# 04_Inputs_19-27.net
KiCad netlist of a schematic drawn in Altium Designer
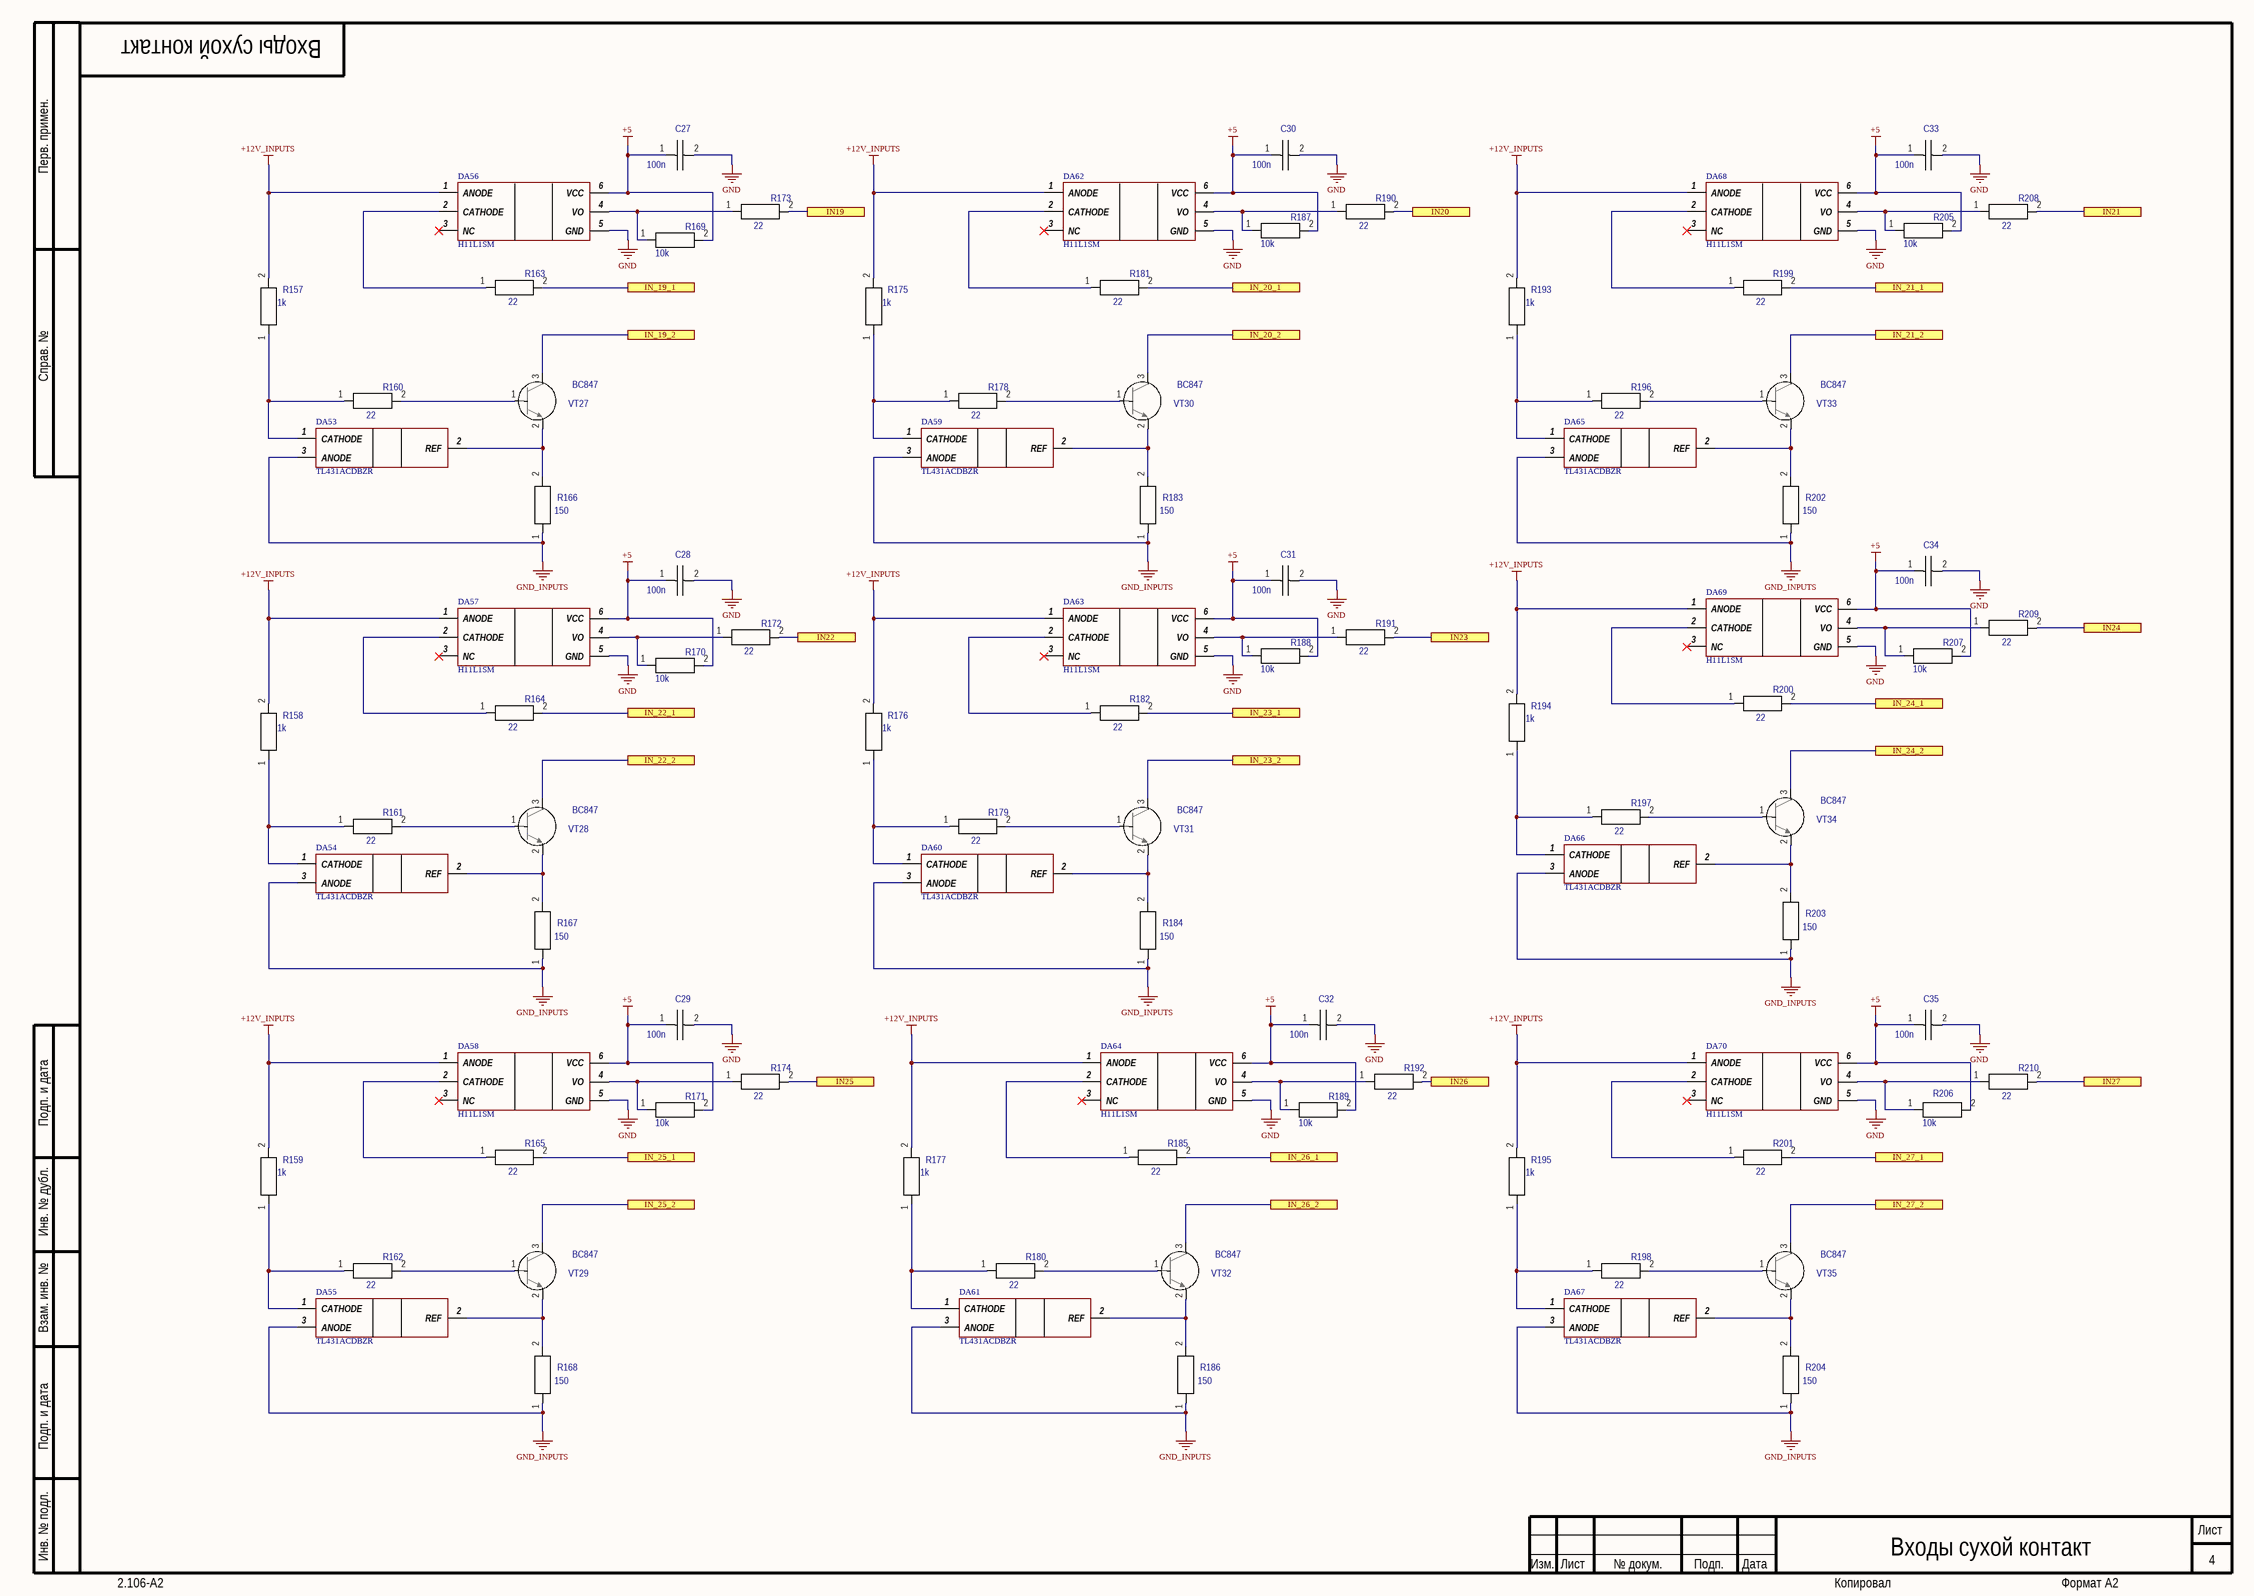
[diagram p0: 04_Inputs_19-27.SchDoc]

(export (version "E")
  (design (tool "Eeschema 10.0.6"))
  (components
    (comp (ref "C27")
      (value "100n")
      (footprint "C0603")
      (fields
        (field (name "PART NUMBER") "GRM188R71C104KA01D")
        (field (name "TOLERANCE") "±10%")
        (field (name "MANUFACTURER") "Murata Manufacturing")
      )
      (libsource (lib "AccessLibrary") (part "Capacitor"))
    )
    (comp (ref "C28")
      (value "100n")
      (footprint "C0603")
      (fields
        (field (name "PART NUMBER") "GRM188R71C104KA01D")
        (field (name "TOLERANCE") "±10%")
        (field (name "MANUFACTURER") "Murata Manufacturing")
      )
      (libsource (lib "AccessLibrary") (part "Capacitor"))
    )
    (comp (ref "C29")
      (value "100n")
      (footprint "C0603")
      (fields
        (field (name "PART NUMBER") "GRM188R71C104KA01D")
        (field (name "TOLERANCE") "±10%")
        (field (name "MANUFACTURER") "Murata Manufacturing")
      )
      (libsource (lib "AccessLibrary") (part "Capacitor"))
    )
    (comp (ref "C30")
      (value "100n")
      (footprint "C0603")
      (fields
        (field (name "PART NUMBER") "GRM188R71C104KA01D")
        (field (name "TOLERANCE") "±10%")
        (field (name "MANUFACTURER") "Murata Manufacturing")
      )
      (libsource (lib "AccessLibrary") (part "Capacitor"))
    )
    (comp (ref "C31")
      (value "100n")
      (footprint "C0603")
      (fields
        (field (name "PART NUMBER") "GRM188R71C104KA01D")
        (field (name "TOLERANCE") "±10%")
        (field (name "MANUFACTURER") "Murata Manufacturing")
      )
      (libsource (lib "AccessLibrary") (part "Capacitor"))
    )
    (comp (ref "C32")
      (value "100n")
      (footprint "C0603")
      (fields
        (field (name "PART NUMBER") "GRM188R71C104KA01D")
        (field (name "TOLERANCE") "±10%")
        (field (name "MANUFACTURER") "Murata Manufacturing")
      )
      (libsource (lib "AccessLibrary") (part "Capacitor"))
    )
    (comp (ref "C33")
      (value "100n")
      (footprint "C0603")
      (fields
        (field (name "PART NUMBER") "GRM188R71C104KA01D")
        (field (name "TOLERANCE") "±10%")
        (field (name "MANUFACTURER") "Murata Manufacturing")
      )
      (libsource (lib "AccessLibrary") (part "Capacitor"))
    )
    (comp (ref "C34")
      (value "100n")
      (footprint "C0603")
      (fields
        (field (name "PART NUMBER") "GRM188R71C104KA01D")
        (field (name "TOLERANCE") "±10%")
        (field (name "MANUFACTURER") "Murata Manufacturing")
      )
      (libsource (lib "AccessLibrary") (part "Capacitor"))
    )
    (comp (ref "C35")
      (value "100n")
      (footprint "C0603")
      (fields
        (field (name "PART NUMBER") "GRM188R71C104KA01D")
        (field (name "TOLERANCE") "±10%")
        (field (name "MANUFACTURER") "Murata Manufacturing")
      )
      (libsource (lib "AccessLibrary") (part "Capacitor"))
    )
    (comp (ref "DA53")
      (value "TL431ACDBZR")
      (footprint "board:SOT95P237X112-3N")
      (description "Integrated Circuit")
      (fields (field (name "MOUSER PART NUMBER") "595-TL431ACDBZR"))
      (libsource (lib "board") (part "TL431ACDBZR"))
    )
    (comp (ref "DA54")
      (value "TL431ACDBZR")
      (footprint "board:SOT95P237X112-3N")
      (description "Integrated Circuit")
      (fields (field (name "MOUSER PART NUMBER") "595-TL431ACDBZR"))
      (libsource (lib "board") (part "TL431ACDBZR"))
    )
    (comp (ref "DA55")
      (value "TL431ACDBZR")
      (footprint "board:SOT95P237X112-3N")
      (description "Integrated Circuit")
      (fields (field (name "MOUSER PART NUMBER") "595-TL431ACDBZR"))
      (libsource (lib "board") (part "TL431ACDBZR"))
    )
    (comp (ref "DA56")
      (value "H11L1SM")
      (footprint "board:SOP254P1030X460-6N")
      (description "Integrated Circuit")
      (libsource (lib "board") (part "H11L1SM"))
    )
    (comp (ref "DA57")
      (value "H11L1SM")
      (footprint "board:SOP254P1030X460-6N")
      (description "Integrated Circuit")
      (libsource (lib "board") (part "H11L1SM"))
    )
    (comp (ref "DA58")
      (value "H11L1SM")
      (footprint "board:SOP254P1030X460-6N")
      (description "Integrated Circuit")
      (libsource (lib "board") (part "H11L1SM"))
    )
    (comp (ref "DA59")
      (value "TL431ACDBZR")
      (footprint "board:SOT95P237X112-3N")
      (description "Integrated Circuit")
      (fields (field (name "MOUSER PART NUMBER") "595-TL431ACDBZR"))
      (libsource (lib "board") (part "TL431ACDBZR"))
    )
    (comp (ref "DA60")
      (value "TL431ACDBZR")
      (footprint "board:SOT95P237X112-3N")
      (description "Integrated Circuit")
      (fields (field (name "MOUSER PART NUMBER") "595-TL431ACDBZR"))
      (libsource (lib "board") (part "TL431ACDBZR"))
    )
    (comp (ref "DA61")
      (value "TL431ACDBZR")
      (footprint "board:SOT95P237X112-3N")
      (description "Integrated Circuit")
      (fields (field (name "MOUSER PART NUMBER") "595-TL431ACDBZR"))
      (libsource (lib "board") (part "TL431ACDBZR"))
    )
    (comp (ref "DA62")
      (value "H11L1SM")
      (footprint "board:SOP254P1030X460-6N")
      (description "Integrated Circuit")
      (libsource (lib "board") (part "H11L1SM"))
    )
    (comp (ref "DA63")
      (value "H11L1SM")
      (footprint "board:SOP254P1030X460-6N")
      (description "Integrated Circuit")
      (libsource (lib "board") (part "H11L1SM"))
    )
    (comp (ref "DA64")
      (value "H11L1SM")
      (footprint "board:SOP254P1030X460-6N")
      (description "Integrated Circuit")
      (libsource (lib "board") (part "H11L1SM"))
    )
    (comp (ref "DA65")
      (value "TL431ACDBZR")
      (footprint "board:SOT95P237X112-3N")
      (description "Integrated Circuit")
      (fields (field (name "MOUSER PART NUMBER") "595-TL431ACDBZR"))
      (libsource (lib "board") (part "TL431ACDBZR"))
    )
    (comp (ref "DA66")
      (value "TL431ACDBZR")
      (footprint "board:SOT95P237X112-3N")
      (description "Integrated Circuit")
      (fields (field (name "MOUSER PART NUMBER") "595-TL431ACDBZR"))
      (libsource (lib "board") (part "TL431ACDBZR"))
    )
    (comp (ref "DA67")
      (value "TL431ACDBZR")
      (footprint "board:SOT95P237X112-3N")
      (description "Integrated Circuit")
      (fields (field (name "MOUSER PART NUMBER") "595-TL431ACDBZR"))
      (libsource (lib "board") (part "TL431ACDBZR"))
    )
    (comp (ref "DA68")
      (value "H11L1SM")
      (footprint "board:SOP254P1030X460-6N")
      (description "Integrated Circuit")
      (libsource (lib "board") (part "H11L1SM"))
    )
    (comp (ref "DA69")
      (value "H11L1SM")
      (footprint "board:SOP254P1030X460-6N")
      (description "Integrated Circuit")
      (libsource (lib "board") (part "H11L1SM"))
    )
    (comp (ref "DA70")
      (value "H11L1SM")
      (footprint "board:SOP254P1030X460-6N")
      (description "Integrated Circuit")
      (libsource (lib "board") (part "H11L1SM"))
    )
    (comp (ref "R157")
      (value "1k")
      (footprint "RESC1608N")
      (fields
        (field (name "PART NUMBER") "RC0603FK-071KL")
        (field (name "TOLERANCE") "±1%")
        (field (name "MANUFACTURER") "Тайвань")
      )
      (libsource (lib "AccessLibrary") (part "Resistor"))
    )
    (comp (ref "R158")
      (value "1k")
      (footprint "RESC1608N")
      (fields
        (field (name "PART NUMBER") "RC0603FK-071KL")
        (field (name "TOLERANCE") "±1%")
        (field (name "MANUFACTURER") "Тайвань")
      )
      (libsource (lib "AccessLibrary") (part "Resistor"))
    )
    (comp (ref "R159")
      (value "1k")
      (footprint "RESC1608N")
      (fields
        (field (name "PART NUMBER") "RC0603FK-071KL")
        (field (name "TOLERANCE") "±1%")
        (field (name "MANUFACTURER") "Тайвань")
      )
      (libsource (lib "AccessLibrary") (part "Resistor"))
    )
    (comp (ref "R160")
      (value "22")
      (footprint "RESC1608N")
      (fields
        (field (name "PART NUMBER") "RC0603FK-0722RL")
        (field (name "TOLERANCE") "±1%")
        (field (name "MANUFACTURER") "Тайвань")
      )
      (libsource (lib "AccessLibrary") (part "Resistor"))
    )
    (comp (ref "R161")
      (value "22")
      (footprint "RESC1608N")
      (fields
        (field (name "PART NUMBER") "RC0603FK-0722RL")
        (field (name "TOLERANCE") "±1%")
        (field (name "MANUFACTURER") "Тайвань")
      )
      (libsource (lib "AccessLibrary") (part "Resistor"))
    )
    (comp (ref "R162")
      (value "22")
      (footprint "RESC1608N")
      (fields
        (field (name "PART NUMBER") "RC0603FK-0722RL")
        (field (name "TOLERANCE") "±1%")
        (field (name "MANUFACTURER") "Тайвань")
      )
      (libsource (lib "AccessLibrary") (part "Resistor"))
    )
    (comp (ref "R163")
      (value "22")
      (footprint "RESC1608N")
      (fields
        (field (name "PART NUMBER") "RC0603FK-0722RL")
        (field (name "TOLERANCE") "±1%")
        (field (name "MANUFACTURER") "Тайвань")
      )
      (libsource (lib "AccessLibrary") (part "Resistor"))
    )
    (comp (ref "R164")
      (value "22")
      (footprint "RESC1608N")
      (fields
        (field (name "PART NUMBER") "RC0603FK-0722RL")
        (field (name "TOLERANCE") "±1%")
        (field (name "MANUFACTURER") "Тайвань")
      )
      (libsource (lib "AccessLibrary") (part "Resistor"))
    )
    (comp (ref "R165")
      (value "22")
      (footprint "RESC1608N")
      (fields
        (field (name "PART NUMBER") "RC0603FK-0722RL")
        (field (name "TOLERANCE") "±1%")
        (field (name "MANUFACTURER") "Тайвань")
      )
      (libsource (lib "AccessLibrary") (part "Resistor"))
    )
    (comp (ref "R166")
      (value "150")
      (footprint "RESC1608N")
      (fields
        (field (name "PART NUMBER") "RC0603FK-07150RL")
        (field (name "TOLERANCE") "±1%")
        (field (name "MANUFACTURER") "Тайвань")
      )
      (libsource (lib "AccessLibrary") (part "Resistor"))
    )
    (comp (ref "R167")
      (value "150")
      (footprint "RESC1608N")
      (fields
        (field (name "PART NUMBER") "RC0603FK-07150RL")
        (field (name "TOLERANCE") "±1%")
        (field (name "MANUFACTURER") "Тайвань")
      )
      (libsource (lib "AccessLibrary") (part "Resistor"))
    )
    (comp (ref "R168")
      (value "150")
      (footprint "RESC1608N")
      (fields
        (field (name "PART NUMBER") "RC0603FK-07150RL")
        (field (name "TOLERANCE") "±1%")
        (field (name "MANUFACTURER") "Тайвань")
      )
      (libsource (lib "AccessLibrary") (part "Resistor"))
    )
    (comp (ref "R169")
      (value "10k")
      (footprint "RESC1608N")
      (fields
        (field (name "PART NUMBER") "RC0603FR-0710KL")
        (field (name "TOLERANCE") "±1%")
        (field (name "MANUFACTURER") "Тайвань")
      )
      (libsource (lib "AccessLibrary") (part "Resistor"))
    )
    (comp (ref "R170")
      (value "10k")
      (footprint "RESC1608N")
      (fields
        (field (name "PART NUMBER") "RC0603FR-0710KL")
        (field (name "TOLERANCE") "±1%")
        (field (name "MANUFACTURER") "Тайвань")
      )
      (libsource (lib "AccessLibrary") (part "Resistor"))
    )
    (comp (ref "R171")
      (value "10k")
      (footprint "RESC1608N")
      (fields
        (field (name "PART NUMBER") "RC0603FR-0710KL")
        (field (name "TOLERANCE") "±1%")
        (field (name "MANUFACTURER") "Тайвань")
      )
      (libsource (lib "AccessLibrary") (part "Resistor"))
    )
    (comp (ref "R172")
      (value "22")
      (footprint "RESC1608N")
      (fields
        (field (name "PART NUMBER") "RC0603FK-0722RL")
        (field (name "TOLERANCE") "±1%")
        (field (name "MANUFACTURER") "Тайвань")
      )
      (libsource (lib "AccessLibrary") (part "Resistor"))
    )
    (comp (ref "R173")
      (value "22")
      (footprint "RESC1608N")
      (fields
        (field (name "PART NUMBER") "RC0603FK-0722RL")
        (field (name "TOLERANCE") "±1%")
        (field (name "MANUFACTURER") "Тайвань")
      )
      (libsource (lib "AccessLibrary") (part "Resistor"))
    )
    (comp (ref "R174")
      (value "22")
      (footprint "RESC1608N")
      (fields
        (field (name "PART NUMBER") "RC0603FK-0722RL")
        (field (name "TOLERANCE") "±1%")
        (field (name "MANUFACTURER") "Тайвань")
      )
      (libsource (lib "AccessLibrary") (part "Resistor"))
    )
    (comp (ref "R175")
      (value "1k")
      (footprint "RESC1608N")
      (fields
        (field (name "PART NUMBER") "RC0603FK-071KL")
        (field (name "TOLERANCE") "±1%")
        (field (name "MANUFACTURER") "Тайвань")
      )
      (libsource (lib "AccessLibrary") (part "Resistor"))
    )
    (comp (ref "R176")
      (value "1k")
      (footprint "RESC1608N")
      (fields
        (field (name "PART NUMBER") "RC0603FK-071KL")
        (field (name "TOLERANCE") "±1%")
        (field (name "MANUFACTURER") "Тайвань")
      )
      (libsource (lib "AccessLibrary") (part "Resistor"))
    )
    (comp (ref "R177")
      (value "1k")
      (footprint "RESC1608N")
      (fields
        (field (name "PART NUMBER") "RC0603FK-071KL")
        (field (name "TOLERANCE") "±1%")
        (field (name "MANUFACTURER") "Тайвань")
      )
      (libsource (lib "AccessLibrary") (part "Resistor"))
    )
    (comp (ref "R178")
      (value "22")
      (footprint "RESC1608N")
      (fields
        (field (name "PART NUMBER") "RC0603FK-0722RL")
        (field (name "TOLERANCE") "±1%")
        (field (name "MANUFACTURER") "Тайвань")
      )
      (libsource (lib "AccessLibrary") (part "Resistor"))
    )
    (comp (ref "R179")
      (value "22")
      (footprint "RESC1608N")
      (fields
        (field (name "PART NUMBER") "RC0603FK-0722RL")
        (field (name "TOLERANCE") "±1%")
        (field (name "MANUFACTURER") "Тайвань")
      )
      (libsource (lib "AccessLibrary") (part "Resistor"))
    )
    (comp (ref "R180")
      (value "22")
      (footprint "RESC1608N")
      (fields
        (field (name "PART NUMBER") "RC0603FK-0722RL")
        (field (name "TOLERANCE") "±1%")
        (field (name "MANUFACTURER") "Тайвань")
      )
      (libsource (lib "AccessLibrary") (part "Resistor"))
    )
    (comp (ref "R181")
      (value "22")
      (footprint "RESC1608N")
      (fields
        (field (name "PART NUMBER") "RC0603FK-0722RL")
        (field (name "TOLERANCE") "±1%")
        (field (name "MANUFACTURER") "Тайвань")
      )
      (libsource (lib "AccessLibrary") (part "Resistor"))
    )
    (comp (ref "R182")
      (value "22")
      (footprint "RESC1608N")
      (fields
        (field (name "PART NUMBER") "RC0603FK-0722RL")
        (field (name "TOLERANCE") "±1%")
        (field (name "MANUFACTURER") "Тайвань")
      )
      (libsource (lib "AccessLibrary") (part "Resistor"))
    )
    (comp (ref "R183")
      (value "150")
      (footprint "RESC1608N")
      (fields
        (field (name "PART NUMBER") "RC0603FK-07150RL")
        (field (name "TOLERANCE") "±1%")
        (field (name "MANUFACTURER") "Тайвань")
      )
      (libsource (lib "AccessLibrary") (part "Resistor"))
    )
    (comp (ref "R184")
      (value "150")
      (footprint "RESC1608N")
      (fields
        (field (name "PART NUMBER") "RC0603FK-07150RL")
        (field (name "TOLERANCE") "±1%")
        (field (name "MANUFACTURER") "Тайвань")
      )
      (libsource (lib "AccessLibrary") (part "Resistor"))
    )
    (comp (ref "R185")
      (value "22")
      (footprint "RESC1608N")
      (fields
        (field (name "PART NUMBER") "RC0603FK-0722RL")
        (field (name "TOLERANCE") "±1%")
        (field (name "MANUFACTURER") "Тайвань")
      )
      (libsource (lib "AccessLibrary") (part "Resistor"))
    )
    (comp (ref "R186")
      (value "150")
      (footprint "RESC1608N")
      (fields
        (field (name "PART NUMBER") "RC0603FK-07150RL")
        (field (name "TOLERANCE") "±1%")
        (field (name "MANUFACTURER") "Тайвань")
      )
      (libsource (lib "AccessLibrary") (part "Resistor"))
    )
    (comp (ref "R187")
      (value "10k")
      (footprint "RESC1608N")
      (fields
        (field (name "PART NUMBER") "RC0603FR-0710KL")
        (field (name "TOLERANCE") "±1%")
        (field (name "MANUFACTURER") "Тайвань")
      )
      (libsource (lib "AccessLibrary") (part "Resistor"))
    )
    (comp (ref "R188")
      (value "10k")
      (footprint "RESC1608N")
      (fields
        (field (name "PART NUMBER") "RC0603FR-0710KL")
        (field (name "TOLERANCE") "±1%")
        (field (name "MANUFACTURER") "Тайвань")
      )
      (libsource (lib "AccessLibrary") (part "Resistor"))
    )
    (comp (ref "R189")
      (value "10k")
      (footprint "RESC1608N")
      (fields
        (field (name "PART NUMBER") "RC0603FR-0710KL")
        (field (name "TOLERANCE") "±1%")
        (field (name "MANUFACTURER") "Тайвань")
      )
      (libsource (lib "AccessLibrary") (part "Resistor"))
    )
    (comp (ref "R190")
      (value "22")
      (footprint "RESC1608N")
      (fields
        (field (name "PART NUMBER") "RC0603FK-0722RL")
        (field (name "TOLERANCE") "±1%")
        (field (name "MANUFACTURER") "Тайвань")
      )
      (libsource (lib "AccessLibrary") (part "Resistor"))
    )
    (comp (ref "R191")
      (value "22")
      (footprint "RESC1608N")
      (fields
        (field (name "PART NUMBER") "RC0603FK-0722RL")
        (field (name "TOLERANCE") "±1%")
        (field (name "MANUFACTURER") "Тайвань")
      )
      (libsource (lib "AccessLibrary") (part "Resistor"))
    )
    (comp (ref "R192")
      (value "22")
      (footprint "RESC1608N")
      (fields
        (field (name "PART NUMBER") "RC0603FK-0722RL")
        (field (name "TOLERANCE") "±1%")
        (field (name "MANUFACTURER") "Тайвань")
      )
      (libsource (lib "AccessLibrary") (part "Resistor"))
    )
    (comp (ref "R193")
      (value "1k")
      (footprint "RESC1608N")
      (fields
        (field (name "PART NUMBER") "RC0603FK-071KL")
        (field (name "TOLERANCE") "±1%")
        (field (name "MANUFACTURER") "Тайвань")
      )
      (libsource (lib "AccessLibrary") (part "Resistor"))
    )
    (comp (ref "R194")
      (value "1k")
      (footprint "RESC1608N")
      (fields
        (field (name "PART NUMBER") "RC0603FK-071KL")
        (field (name "TOLERANCE") "±1%")
        (field (name "MANUFACTURER") "Тайвань")
      )
      (libsource (lib "AccessLibrary") (part "Resistor"))
    )
    (comp (ref "R195")
      (value "1k")
      (footprint "RESC1608N")
      (fields
        (field (name "PART NUMBER") "RC0603FK-071KL")
        (field (name "TOLERANCE") "±1%")
        (field (name "MANUFACTURER") "Тайвань")
      )
      (libsource (lib "AccessLibrary") (part "Resistor"))
    )
    (comp (ref "R196")
      (value "22")
      (footprint "RESC1608N")
      (fields
        (field (name "PART NUMBER") "RC0603FK-0722RL")
        (field (name "TOLERANCE") "±1%")
        (field (name "MANUFACTURER") "Тайвань")
      )
      (libsource (lib "AccessLibrary") (part "Resistor"))
    )
    (comp (ref "R197")
      (value "22")
      (footprint "RESC1608N")
      (fields
        (field (name "PART NUMBER") "RC0603FK-0722RL")
        (field (name "TOLERANCE") "±1%")
        (field (name "MANUFACTURER") "Тайвань")
      )
      (libsource (lib "AccessLibrary") (part "Resistor"))
    )
    (comp (ref "R198")
      (value "22")
      (footprint "RESC1608N")
      (fields
        (field (name "PART NUMBER") "RC0603FK-0722RL")
        (field (name "TOLERANCE") "±1%")
        (field (name "MANUFACTURER") "Тайвань")
      )
      (libsource (lib "AccessLibrary") (part "Resistor"))
    )
    (comp (ref "R199")
      (value "22")
      (footprint "RESC1608N")
      (fields
        (field (name "PART NUMBER") "RC0603FK-0722RL")
        (field (name "TOLERANCE") "±1%")
        (field (name "MANUFACTURER") "Тайвань")
      )
      (libsource (lib "AccessLibrary") (part "Resistor"))
    )
    (comp (ref "R200")
      (value "22")
      (footprint "RESC1608N")
      (fields
        (field (name "PART NUMBER") "RC0603FK-0722RL")
        (field (name "TOLERANCE") "±1%")
        (field (name "MANUFACTURER") "Тайвань")
      )
      (libsource (lib "AccessLibrary") (part "Resistor"))
    )
    (comp (ref "R201")
      (value "22")
      (footprint "RESC1608N")
      (fields
        (field (name "PART NUMBER") "RC0603FK-0722RL")
        (field (name "TOLERANCE") "±1%")
        (field (name "MANUFACTURER") "Тайвань")
      )
      (libsource (lib "AccessLibrary") (part "Resistor"))
    )
    (comp (ref "R202")
      (value "150")
      (footprint "RESC1608N")
      (fields
        (field (name "PART NUMBER") "RC0603FK-07150RL")
        (field (name "TOLERANCE") "±1%")
        (field (name "MANUFACTURER") "Тайвань")
      )
      (libsource (lib "AccessLibrary") (part "Resistor"))
    )
    (comp (ref "R203")
      (value "150")
      (footprint "RESC1608N")
      (fields
        (field (name "PART NUMBER") "RC0603FK-07150RL")
        (field (name "TOLERANCE") "±1%")
        (field (name "MANUFACTURER") "Тайвань")
      )
      (libsource (lib "AccessLibrary") (part "Resistor"))
    )
    (comp (ref "R204")
      (value "150")
      (footprint "RESC1608N")
      (fields
        (field (name "PART NUMBER") "RC0603FK-07150RL")
        (field (name "TOLERANCE") "±1%")
        (field (name "MANUFACTURER") "Тайвань")
      )
      (libsource (lib "AccessLibrary") (part "Resistor"))
    )
    (comp (ref "R205")
      (value "10k")
      (footprint "RESC1608N")
      (fields
        (field (name "PART NUMBER") "RC0603FR-0710KL")
        (field (name "TOLERANCE") "±1%")
        (field (name "MANUFACTURER") "Тайвань")
      )
      (libsource (lib "AccessLibrary") (part "Resistor"))
    )
    (comp (ref "R206")
      (value "10k")
      (footprint "RESC1608N")
      (fields
        (field (name "PART NUMBER") "RC0603FR-0710KL")
        (field (name "TOLERANCE") "±1%")
        (field (name "MANUFACTURER") "Тайвань")
      )
      (libsource (lib "AccessLibrary") (part "Resistor"))
    )
    (comp (ref "R207")
      (value "10k")
      (footprint "RESC1608N")
      (fields
        (field (name "PART NUMBER") "RC0603FR-0710KL")
        (field (name "TOLERANCE") "±1%")
        (field (name "MANUFACTURER") "Тайвань")
      )
      (libsource (lib "AccessLibrary") (part "Resistor"))
    )
    (comp (ref "R208")
      (value "22")
      (footprint "RESC1608N")
      (fields
        (field (name "PART NUMBER") "RC0603FK-0722RL")
        (field (name "TOLERANCE") "±1%")
        (field (name "MANUFACTURER") "Тайвань")
      )
      (libsource (lib "AccessLibrary") (part "Resistor"))
    )
    (comp (ref "R209")
      (value "22")
      (footprint "RESC1608N")
      (fields
        (field (name "PART NUMBER") "RC0603FK-0722RL")
        (field (name "TOLERANCE") "±1%")
        (field (name "MANUFACTURER") "Тайвань")
      )
      (libsource (lib "AccessLibrary") (part "Resistor"))
    )
    (comp (ref "R210")
      (value "22")
      (footprint "RESC1608N")
      (fields
        (field (name "PART NUMBER") "RC0603FK-0722RL")
        (field (name "TOLERANCE") "±1%")
        (field (name "MANUFACTURER") "Тайвань")
      )
      (libsource (lib "AccessLibrary") (part "Resistor"))
    )
    (comp (ref "VT27")
      (value "BC847")
      (footprint "SOT23-3N")
      (fields (field (name "COM") "BC847") (field (name "MANUFACTURER") "NXP Semiconductor"))
      (libsource (lib "AccessLibrary") (part "Transistor_npn_1b-2e-3c"))
    )
    (comp (ref "VT28")
      (value "BC847")
      (footprint "SOT23-3N")
      (fields (field (name "COM") "BC847") (field (name "MANUFACTURER") "NXP Semiconductor"))
      (libsource (lib "AccessLibrary") (part "Transistor_npn_1b-2e-3c"))
    )
    (comp (ref "VT29")
      (value "BC847")
      (footprint "SOT23-3N")
      (fields (field (name "COM") "BC847") (field (name "MANUFACTURER") "NXP Semiconductor"))
      (libsource (lib "AccessLibrary") (part "Transistor_npn_1b-2e-3c"))
    )
    (comp (ref "VT30")
      (value "BC847")
      (footprint "SOT23-3N")
      (fields (field (name "COM") "BC847") (field (name "MANUFACTURER") "NXP Semiconductor"))
      (libsource (lib "AccessLibrary") (part "Transistor_npn_1b-2e-3c"))
    )
    (comp (ref "VT31")
      (value "BC847")
      (footprint "SOT23-3N")
      (fields (field (name "COM") "BC847") (field (name "MANUFACTURER") "NXP Semiconductor"))
      (libsource (lib "AccessLibrary") (part "Transistor_npn_1b-2e-3c"))
    )
    (comp (ref "VT32")
      (value "BC847")
      (footprint "SOT23-3N")
      (fields (field (name "COM") "BC847") (field (name "MANUFACTURER") "NXP Semiconductor"))
      (libsource (lib "AccessLibrary") (part "Transistor_npn_1b-2e-3c"))
    )
    (comp (ref "VT33")
      (value "BC847")
      (footprint "SOT23-3N")
      (fields (field (name "COM") "BC847") (field (name "MANUFACTURER") "NXP Semiconductor"))
      (libsource (lib "AccessLibrary") (part "Transistor_npn_1b-2e-3c"))
    )
    (comp (ref "VT34")
      (value "BC847")
      (footprint "SOT23-3N")
      (fields (field (name "COM") "BC847") (field (name "MANUFACTURER") "NXP Semiconductor"))
      (libsource (lib "AccessLibrary") (part "Transistor_npn_1b-2e-3c"))
    )
    (comp (ref "VT35")
      (value "BC847")
      (footprint "SOT23-3N")
      (fields (field (name "COM") "BC847") (field (name "MANUFACTURER") "NXP Semiconductor"))
      (libsource (lib "AccessLibrary") (part "Transistor_npn_1b-2e-3c"))
    )
  )
  (nets
    (net (code "1") (name "+5") (class "Default")
      (node (ref "C27") (pin "1") (pinfunction "1_1") (pintype "passive"))
      (node (ref "C28") (pin "1") (pinfunction "1_1") (pintype "passive"))
      (node (ref "C29") (pin "1") (pinfunction "1_1") (pintype "passive"))
      (node (ref "C30") (pin "1") (pinfunction "1_1") (pintype "passive"))
      (node (ref "C31") (pin "1") (pinfunction "1_1") (pintype "passive"))
      (node (ref "C32") (pin "1") (pinfunction "1_1") (pintype "passive"))
      (node (ref "C33") (pin "1") (pinfunction "1_1") (pintype "passive"))
      (node (ref "C34") (pin "1") (pinfunction "1_1") (pintype "passive"))
      (node (ref "C35") (pin "1") (pinfunction "1_1") (pintype "passive"))
      (node (ref "DA56") (pin "6") (pinfunction "VCC_6") (pintype "passive"))
      (node (ref "DA57") (pin "6") (pinfunction "VCC_6") (pintype "passive"))
      (node (ref "DA58") (pin "6") (pinfunction "VCC_6") (pintype "passive"))
      (node (ref "DA62") (pin "6") (pinfunction "VCC_6") (pintype "passive"))
      (node (ref "DA63") (pin "6") (pinfunction "VCC_6") (pintype "passive"))
      (node (ref "DA64") (pin "6") (pinfunction "VCC_6") (pintype "passive"))
      (node (ref "DA68") (pin "6") (pinfunction "VCC_6") (pintype "passive"))
      (node (ref "DA69") (pin "6") (pinfunction "VCC_6") (pintype "passive"))
      (node (ref "DA70") (pin "6") (pinfunction "VCC_6") (pintype "passive"))
      (node (ref "R169") (pin "2") (pinfunction "2_2") (pintype "passive"))
      (node (ref "R170") (pin "2") (pinfunction "2_2") (pintype "passive"))
      (node (ref "R171") (pin "2") (pinfunction "2_2") (pintype "passive"))
      (node (ref "R187") (pin "2") (pinfunction "2_2") (pintype "passive"))
      (node (ref "R188") (pin "2") (pinfunction "2_2") (pintype "passive"))
      (node (ref "R189") (pin "2") (pinfunction "2_2") (pintype "passive"))
      (node (ref "R205") (pin "2") (pinfunction "2_2") (pintype "passive"))
      (node (ref "R206") (pin "2") (pinfunction "2_2") (pintype "passive"))
      (node (ref "R207") (pin "2") (pinfunction "2_2") (pintype "passive"))
    )
    (net (code "2") (name "+12V_INPUTS") (class "Default")
      (node (ref "DA56") (pin "1") (pinfunction "ANODE_1") (pintype "passive"))
      (node (ref "DA57") (pin "1") (pinfunction "ANODE_1") (pintype "passive"))
      (node (ref "DA58") (pin "1") (pinfunction "ANODE_1") (pintype "passive"))
      (node (ref "DA62") (pin "1") (pinfunction "ANODE_1") (pintype "passive"))
      (node (ref "DA63") (pin "1") (pinfunction "ANODE_1") (pintype "passive"))
      (node (ref "DA64") (pin "1") (pinfunction "ANODE_1") (pintype "passive"))
      (node (ref "DA68") (pin "1") (pinfunction "ANODE_1") (pintype "passive"))
      (node (ref "DA69") (pin "1") (pinfunction "ANODE_1") (pintype "passive"))
      (node (ref "DA70") (pin "1") (pinfunction "ANODE_1") (pintype "passive"))
      (node (ref "R157") (pin "2") (pinfunction "2_2") (pintype "passive"))
      (node (ref "R158") (pin "2") (pinfunction "2_2") (pintype "passive"))
      (node (ref "R159") (pin "2") (pinfunction "2_2") (pintype "passive"))
      (node (ref "R175") (pin "2") (pinfunction "2_2") (pintype "passive"))
      (node (ref "R176") (pin "2") (pinfunction "2_2") (pintype "passive"))
      (node (ref "R177") (pin "2") (pinfunction "2_2") (pintype "passive"))
      (node (ref "R193") (pin "2") (pinfunction "2_2") (pintype "passive"))
      (node (ref "R194") (pin "2") (pinfunction "2_2") (pintype "passive"))
      (node (ref "R195") (pin "2") (pinfunction "2_2") (pintype "passive"))
    )
    (net (code "3") (name "/IN19") (class "Default")
      (node (ref "R173") (pin "2") (pinfunction "2_2") (pintype "passive"))
    )
    (net (code "4") (name "/IN20") (class "Default")
      (node (ref "R190") (pin "2") (pinfunction "2_2") (pintype "passive"))
    )
    (net (code "5") (name "/IN21") (class "Default")
      (node (ref "R208") (pin "2") (pinfunction "2_2") (pintype "passive"))
    )
    (net (code "6") (name "/IN22") (class "Default")
      (node (ref "R172") (pin "2") (pinfunction "2_2") (pintype "passive"))
    )
    (net (code "7") (name "/IN23") (class "Default")
      (node (ref "R191") (pin "2") (pinfunction "2_2") (pintype "passive"))
    )
    (net (code "8") (name "/IN24") (class "Default")
      (node (ref "R209") (pin "2") (pinfunction "2_2") (pintype "passive"))
    )
    (net (code "9") (name "/IN25") (class "Default")
      (node (ref "R174") (pin "2") (pinfunction "2_2") (pintype "passive"))
    )
    (net (code "10") (name "/IN26") (class "Default")
      (node (ref "R192") (pin "2") (pinfunction "2_2") (pintype "passive"))
    )
    (net (code "11") (name "/IN27") (class "Default")
      (node (ref "R210") (pin "2") (pinfunction "2_2") (pintype "passive"))
    )
    (net (code "12") (name "/IN_19_1") (class "Default")
      (node (ref "R163") (pin "2") (pinfunction "2_2") (pintype "passive"))
    )
    (net (code "13") (name "/IN_19_2") (class "Default")
      (node (ref "VT27") (pin "3") (pinfunction "3_3") (pintype "passive"))
    )
    (net (code "14") (name "/IN_20_1") (class "Default")
      (node (ref "R181") (pin "2") (pinfunction "2_2") (pintype "passive"))
    )
    (net (code "15") (name "/IN_20_2") (class "Default")
      (node (ref "VT30") (pin "3") (pinfunction "3_3") (pintype "passive"))
    )
    (net (code "16") (name "/IN_21_1") (class "Default")
      (node (ref "R199") (pin "2") (pinfunction "2_2") (pintype "passive"))
    )
    (net (code "17") (name "/IN_21_2") (class "Default")
      (node (ref "VT33") (pin "3") (pinfunction "3_3") (pintype "passive"))
    )
    (net (code "18") (name "/IN_22_1") (class "Default")
      (node (ref "R164") (pin "2") (pinfunction "2_2") (pintype "passive"))
    )
    (net (code "19") (name "/IN_22_2") (class "Default")
      (node (ref "VT28") (pin "3") (pinfunction "3_3") (pintype "passive"))
    )
    (net (code "20") (name "/IN_23_1") (class "Default")
      (node (ref "R182") (pin "2") (pinfunction "2_2") (pintype "passive"))
    )
    (net (code "21") (name "/IN_23_2") (class "Default")
      (node (ref "VT31") (pin "3") (pinfunction "3_3") (pintype "passive"))
    )
    (net (code "22") (name "/IN_24_1") (class "Default")
      (node (ref "R200") (pin "2") (pinfunction "2_2") (pintype "passive"))
    )
    (net (code "23") (name "/IN_24_2") (class "Default")
      (node (ref "VT34") (pin "3") (pinfunction "3_3") (pintype "passive"))
    )
    (net (code "24") (name "/IN_25_1") (class "Default")
      (node (ref "R165") (pin "2") (pinfunction "2_2") (pintype "passive"))
    )
    (net (code "25") (name "/IN_25_2") (class "Default")
      (node (ref "VT29") (pin "3") (pinfunction "3_3") (pintype "passive"))
    )
    (net (code "26") (name "/IN_26_1") (class "Default")
      (node (ref "R185") (pin "2") (pinfunction "2_2") (pintype "passive"))
    )
    (net (code "27") (name "/IN_26_2") (class "Default")
      (node (ref "VT32") (pin "3") (pinfunction "3_3") (pintype "passive"))
    )
    (net (code "28") (name "/IN_27_1") (class "Default")
      (node (ref "R201") (pin "2") (pinfunction "2_2") (pintype "passive"))
    )
    (net (code "29") (name "/IN_27_2") (class "Default")
      (node (ref "VT35") (pin "3") (pinfunction "3_3") (pintype "passive"))
    )
    (net (code "30") (name "GND") (class "Default")
      (node (ref "C27") (pin "2") (pinfunction "2_2") (pintype "passive"))
      (node (ref "C28") (pin "2") (pinfunction "2_2") (pintype "passive"))
      (node (ref "C29") (pin "2") (pinfunction "2_2") (pintype "passive"))
      (node (ref "C30") (pin "2") (pinfunction "2_2") (pintype "passive"))
      (node (ref "C31") (pin "2") (pinfunction "2_2") (pintype "passive"))
      (node (ref "C32") (pin "2") (pinfunction "2_2") (pintype "passive"))
      (node (ref "C33") (pin "2") (pinfunction "2_2") (pintype "passive"))
      (node (ref "C34") (pin "2") (pinfunction "2_2") (pintype "passive"))
      (node (ref "C35") (pin "2") (pinfunction "2_2") (pintype "passive"))
      (node (ref "DA56") (pin "5") (pinfunction "GND_5") (pintype "passive"))
      (node (ref "DA57") (pin "5") (pinfunction "GND_5") (pintype "passive"))
      (node (ref "DA58") (pin "5") (pinfunction "GND_5") (pintype "passive"))
      (node (ref "DA62") (pin "5") (pinfunction "GND_5") (pintype "passive"))
      (node (ref "DA63") (pin "5") (pinfunction "GND_5") (pintype "passive"))
      (node (ref "DA64") (pin "5") (pinfunction "GND_5") (pintype "passive"))
      (node (ref "DA68") (pin "5") (pinfunction "GND_5") (pintype "passive"))
      (node (ref "DA69") (pin "5") (pinfunction "GND_5") (pintype "passive"))
      (node (ref "DA70") (pin "5") (pinfunction "GND_5") (pintype "passive"))
    )
    (net (code "31") (name "GND_INPUTS") (class "Default")
      (node (ref "DA53") (pin "3") (pinfunction "ANODE_3") (pintype "passive"))
      (node (ref "DA54") (pin "3") (pinfunction "ANODE_3") (pintype "passive"))
      (node (ref "DA55") (pin "3") (pinfunction "ANODE_3") (pintype "passive"))
      (node (ref "DA59") (pin "3") (pinfunction "ANODE_3") (pintype "passive"))
      (node (ref "DA60") (pin "3") (pinfunction "ANODE_3") (pintype "passive"))
      (node (ref "DA61") (pin "3") (pinfunction "ANODE_3") (pintype "passive"))
      (node (ref "DA65") (pin "3") (pinfunction "ANODE_3") (pintype "passive"))
      (node (ref "DA66") (pin "3") (pinfunction "ANODE_3") (pintype "passive"))
      (node (ref "DA67") (pin "3") (pinfunction "ANODE_3") (pintype "passive"))
      (node (ref "R166") (pin "1") (pinfunction "1_1") (pintype "passive"))
      (node (ref "R167") (pin "1") (pinfunction "1_1") (pintype "passive"))
      (node (ref "R168") (pin "1") (pinfunction "1_1") (pintype "passive"))
      (node (ref "R183") (pin "1") (pinfunction "1_1") (pintype "passive"))
      (node (ref "R184") (pin "1") (pinfunction "1_1") (pintype "passive"))
      (node (ref "R186") (pin "1") (pinfunction "1_1") (pintype "passive"))
      (node (ref "R202") (pin "1") (pinfunction "1_1") (pintype "passive"))
      (node (ref "R203") (pin "1") (pinfunction "1_1") (pintype "passive"))
      (node (ref "R204") (pin "1") (pinfunction "1_1") (pintype "passive"))
    )
    (net (code "32") (name "Net-(DA53-CATHODE)") (class "Default")
      (node (ref "DA53") (pin "1") (pinfunction "CATHODE_1") (pintype "passive"))
      (node (ref "R157") (pin "1") (pinfunction "1_1") (pintype "passive"))
      (node (ref "R160") (pin "1") (pinfunction "1_1") (pintype "passive"))
    )
    (net (code "33") (name "Net-(DA53-REF)") (class "Default")
      (node (ref "DA53") (pin "2") (pinfunction "REF_2") (pintype "passive"))
      (node (ref "R166") (pin "2") (pinfunction "2_2") (pintype "passive"))
      (node (ref "VT27") (pin "2") (pinfunction "2_2") (pintype "passive"))
    )
    (net (code "34") (name "Net-(DA54-CATHODE)") (class "Default")
      (node (ref "DA54") (pin "1") (pinfunction "CATHODE_1") (pintype "passive"))
      (node (ref "R158") (pin "1") (pinfunction "1_1") (pintype "passive"))
      (node (ref "R161") (pin "1") (pinfunction "1_1") (pintype "passive"))
    )
    (net (code "35") (name "Net-(DA54-REF)") (class "Default")
      (node (ref "DA54") (pin "2") (pinfunction "REF_2") (pintype "passive"))
      (node (ref "R167") (pin "2") (pinfunction "2_2") (pintype "passive"))
      (node (ref "VT28") (pin "2") (pinfunction "2_2") (pintype "passive"))
    )
    (net (code "36") (name "Net-(DA55-CATHODE)") (class "Default")
      (node (ref "DA55") (pin "1") (pinfunction "CATHODE_1") (pintype "passive"))
      (node (ref "R159") (pin "1") (pinfunction "1_1") (pintype "passive"))
      (node (ref "R162") (pin "1") (pinfunction "1_1") (pintype "passive"))
    )
    (net (code "37") (name "Net-(DA55-REF)") (class "Default")
      (node (ref "DA55") (pin "2") (pinfunction "REF_2") (pintype "passive"))
      (node (ref "R168") (pin "2") (pinfunction "2_2") (pintype "passive"))
      (node (ref "VT29") (pin "2") (pinfunction "2_2") (pintype "passive"))
    )
    (net (code "38") (name "Net-(DA56-CATHODE)") (class "Default")
      (node (ref "DA56") (pin "2") (pinfunction "CATHODE_2") (pintype "passive"))
      (node (ref "R163") (pin "1") (pinfunction "1_1") (pintype "passive"))
    )
    (net (code "39") (name "Net-(DA56-VO)") (class "Default")
      (node (ref "DA56") (pin "4") (pinfunction "VO_4") (pintype "passive"))
      (node (ref "R169") (pin "1") (pinfunction "1_1") (pintype "passive"))
      (node (ref "R173") (pin "1") (pinfunction "1_1") (pintype "passive"))
    )
    (net (code "40") (name "Net-(DA57-CATHODE)") (class "Default")
      (node (ref "DA57") (pin "2") (pinfunction "CATHODE_2") (pintype "passive"))
      (node (ref "R164") (pin "1") (pinfunction "1_1") (pintype "passive"))
    )
    (net (code "41") (name "Net-(DA57-VO)") (class "Default")
      (node (ref "DA57") (pin "4") (pinfunction "VO_4") (pintype "passive"))
      (node (ref "R170") (pin "1") (pinfunction "1_1") (pintype "passive"))
      (node (ref "R172") (pin "1") (pinfunction "1_1") (pintype "passive"))
    )
    (net (code "42") (name "Net-(DA58-CATHODE)") (class "Default")
      (node (ref "DA58") (pin "2") (pinfunction "CATHODE_2") (pintype "passive"))
      (node (ref "R165") (pin "1") (pinfunction "1_1") (pintype "passive"))
    )
    (net (code "43") (name "Net-(DA58-VO)") (class "Default")
      (node (ref "DA58") (pin "4") (pinfunction "VO_4") (pintype "passive"))
      (node (ref "R171") (pin "1") (pinfunction "1_1") (pintype "passive"))
      (node (ref "R174") (pin "1") (pinfunction "1_1") (pintype "passive"))
    )
    (net (code "44") (name "Net-(DA59-CATHODE)") (class "Default")
      (node (ref "DA59") (pin "1") (pinfunction "CATHODE_1") (pintype "passive"))
      (node (ref "R175") (pin "1") (pinfunction "1_1") (pintype "passive"))
      (node (ref "R178") (pin "1") (pinfunction "1_1") (pintype "passive"))
    )
    (net (code "45") (name "Net-(DA59-REF)") (class "Default")
      (node (ref "DA59") (pin "2") (pinfunction "REF_2") (pintype "passive"))
      (node (ref "R183") (pin "2") (pinfunction "2_2") (pintype "passive"))
      (node (ref "VT30") (pin "2") (pinfunction "2_2") (pintype "passive"))
    )
    (net (code "46") (name "Net-(DA60-CATHODE)") (class "Default")
      (node (ref "DA60") (pin "1") (pinfunction "CATHODE_1") (pintype "passive"))
      (node (ref "R176") (pin "1") (pinfunction "1_1") (pintype "passive"))
      (node (ref "R179") (pin "1") (pinfunction "1_1") (pintype "passive"))
    )
    (net (code "47") (name "Net-(DA60-REF)") (class "Default")
      (node (ref "DA60") (pin "2") (pinfunction "REF_2") (pintype "passive"))
      (node (ref "R184") (pin "2") (pinfunction "2_2") (pintype "passive"))
      (node (ref "VT31") (pin "2") (pinfunction "2_2") (pintype "passive"))
    )
    (net (code "48") (name "Net-(DA61-CATHODE)") (class "Default")
      (node (ref "DA61") (pin "1") (pinfunction "CATHODE_1") (pintype "passive"))
      (node (ref "R177") (pin "1") (pinfunction "1_1") (pintype "passive"))
      (node (ref "R180") (pin "1") (pinfunction "1_1") (pintype "passive"))
    )
    (net (code "49") (name "Net-(DA61-REF)") (class "Default")
      (node (ref "DA61") (pin "2") (pinfunction "REF_2") (pintype "passive"))
      (node (ref "R186") (pin "2") (pinfunction "2_2") (pintype "passive"))
      (node (ref "VT32") (pin "2") (pinfunction "2_2") (pintype "passive"))
    )
    (net (code "50") (name "Net-(DA62-CATHODE)") (class "Default")
      (node (ref "DA62") (pin "2") (pinfunction "CATHODE_2") (pintype "passive"))
      (node (ref "R181") (pin "1") (pinfunction "1_1") (pintype "passive"))
    )
    (net (code "51") (name "Net-(DA62-VO)") (class "Default")
      (node (ref "DA62") (pin "4") (pinfunction "VO_4") (pintype "passive"))
      (node (ref "R187") (pin "1") (pinfunction "1_1") (pintype "passive"))
      (node (ref "R190") (pin "1") (pinfunction "1_1") (pintype "passive"))
    )
    (net (code "52") (name "Net-(DA63-CATHODE)") (class "Default")
      (node (ref "DA63") (pin "2") (pinfunction "CATHODE_2") (pintype "passive"))
      (node (ref "R182") (pin "1") (pinfunction "1_1") (pintype "passive"))
    )
    (net (code "53") (name "Net-(DA63-VO)") (class "Default")
      (node (ref "DA63") (pin "4") (pinfunction "VO_4") (pintype "passive"))
      (node (ref "R188") (pin "1") (pinfunction "1_1") (pintype "passive"))
      (node (ref "R191") (pin "1") (pinfunction "1_1") (pintype "passive"))
    )
    (net (code "54") (name "Net-(DA64-CATHODE)") (class "Default")
      (node (ref "DA64") (pin "2") (pinfunction "CATHODE_2") (pintype "passive"))
      (node (ref "R185") (pin "1") (pinfunction "1_1") (pintype "passive"))
    )
    (net (code "55") (name "Net-(DA64-VO)") (class "Default")
      (node (ref "DA64") (pin "4") (pinfunction "VO_4") (pintype "passive"))
      (node (ref "R189") (pin "1") (pinfunction "1_1") (pintype "passive"))
      (node (ref "R192") (pin "1") (pinfunction "1_1") (pintype "passive"))
    )
    (net (code "56") (name "Net-(DA65-CATHODE)") (class "Default")
      (node (ref "DA65") (pin "1") (pinfunction "CATHODE_1") (pintype "passive"))
      (node (ref "R193") (pin "1") (pinfunction "1_1") (pintype "passive"))
      (node (ref "R196") (pin "1") (pinfunction "1_1") (pintype "passive"))
    )
    (net (code "57") (name "Net-(DA65-REF)") (class "Default")
      (node (ref "DA65") (pin "2") (pinfunction "REF_2") (pintype "passive"))
      (node (ref "R202") (pin "2") (pinfunction "2_2") (pintype "passive"))
      (node (ref "VT33") (pin "2") (pinfunction "2_2") (pintype "passive"))
    )
    (net (code "58") (name "Net-(DA66-CATHODE)") (class "Default")
      (node (ref "DA66") (pin "1") (pinfunction "CATHODE_1") (pintype "passive"))
      (node (ref "R194") (pin "1") (pinfunction "1_1") (pintype "passive"))
      (node (ref "R197") (pin "1") (pinfunction "1_1") (pintype "passive"))
    )
    (net (code "59") (name "Net-(DA66-REF)") (class "Default")
      (node (ref "DA66") (pin "2") (pinfunction "REF_2") (pintype "passive"))
      (node (ref "R203") (pin "2") (pinfunction "2_2") (pintype "passive"))
      (node (ref "VT34") (pin "2") (pinfunction "2_2") (pintype "passive"))
    )
    (net (code "60") (name "Net-(DA67-CATHODE)") (class "Default")
      (node (ref "DA67") (pin "1") (pinfunction "CATHODE_1") (pintype "passive"))
      (node (ref "R195") (pin "1") (pinfunction "1_1") (pintype "passive"))
      (node (ref "R198") (pin "1") (pinfunction "1_1") (pintype "passive"))
    )
    (net (code "61") (name "Net-(DA67-REF)") (class "Default")
      (node (ref "DA67") (pin "2") (pinfunction "REF_2") (pintype "passive"))
      (node (ref "R204") (pin "2") (pinfunction "2_2") (pintype "passive"))
      (node (ref "VT35") (pin "2") (pinfunction "2_2") (pintype "passive"))
    )
    (net (code "62") (name "Net-(DA68-CATHODE)") (class "Default")
      (node (ref "DA68") (pin "2") (pinfunction "CATHODE_2") (pintype "passive"))
      (node (ref "R199") (pin "1") (pinfunction "1_1") (pintype "passive"))
    )
    (net (code "63") (name "Net-(DA68-VO)") (class "Default")
      (node (ref "DA68") (pin "4") (pinfunction "VO_4") (pintype "passive"))
      (node (ref "R205") (pin "1") (pinfunction "1_1") (pintype "passive"))
      (node (ref "R208") (pin "1") (pinfunction "1_1") (pintype "passive"))
    )
    (net (code "64") (name "Net-(DA69-CATHODE)") (class "Default")
      (node (ref "DA69") (pin "2") (pinfunction "CATHODE_2") (pintype "passive"))
      (node (ref "R200") (pin "1") (pinfunction "1_1") (pintype "passive"))
    )
    (net (code "65") (name "Net-(DA69-VO)") (class "Default")
      (node (ref "DA69") (pin "4") (pinfunction "VO_4") (pintype "passive"))
      (node (ref "R207") (pin "1") (pinfunction "1_1") (pintype "passive"))
      (node (ref "R209") (pin "1") (pinfunction "1_1") (pintype "passive"))
    )
    (net (code "66") (name "Net-(DA70-CATHODE)") (class "Default")
      (node (ref "DA70") (pin "2") (pinfunction "CATHODE_2") (pintype "passive"))
      (node (ref "R201") (pin "1") (pinfunction "1_1") (pintype "passive"))
    )
    (net (code "67") (name "Net-(DA70-VO)") (class "Default")
      (node (ref "DA70") (pin "4") (pinfunction "VO_4") (pintype "passive"))
      (node (ref "R206") (pin "1") (pinfunction "1_1") (pintype "passive"))
      (node (ref "R210") (pin "1") (pinfunction "1_1") (pintype "passive"))
    )
    (net (code "68") (name "Net-(R160-Pad2)") (class "Default")
      (node (ref "R160") (pin "2") (pinfunction "2_2") (pintype "passive"))
      (node (ref "VT27") (pin "1") (pinfunction "1_1") (pintype "passive"))
    )
    (net (code "69") (name "Net-(R161-Pad2)") (class "Default")
      (node (ref "R161") (pin "2") (pinfunction "2_2") (pintype "passive"))
      (node (ref "VT28") (pin "1") (pinfunction "1_1") (pintype "passive"))
    )
    (net (code "70") (name "Net-(R162-Pad2)") (class "Default")
      (node (ref "R162") (pin "2") (pinfunction "2_2") (pintype "passive"))
      (node (ref "VT29") (pin "1") (pinfunction "1_1") (pintype "passive"))
    )
    (net (code "71") (name "Net-(R178-Pad2)") (class "Default")
      (node (ref "R178") (pin "2") (pinfunction "2_2") (pintype "passive"))
      (node (ref "VT30") (pin "1") (pinfunction "1_1") (pintype "passive"))
    )
    (net (code "72") (name "Net-(R179-Pad2)") (class "Default")
      (node (ref "R179") (pin "2") (pinfunction "2_2") (pintype "passive"))
      (node (ref "VT31") (pin "1") (pinfunction "1_1") (pintype "passive"))
    )
    (net (code "73") (name "Net-(R180-Pad2)") (class "Default")
      (node (ref "R180") (pin "2") (pinfunction "2_2") (pintype "passive"))
      (node (ref "VT32") (pin "1") (pinfunction "1_1") (pintype "passive"))
    )
    (net (code "74") (name "Net-(R196-Pad2)") (class "Default")
      (node (ref "R196") (pin "2") (pinfunction "2_2") (pintype "passive"))
      (node (ref "VT33") (pin "1") (pinfunction "1_1") (pintype "passive"))
    )
    (net (code "75") (name "Net-(R197-Pad2)") (class "Default")
      (node (ref "R197") (pin "2") (pinfunction "2_2") (pintype "passive"))
      (node (ref "VT34") (pin "1") (pinfunction "1_1") (pintype "passive"))
    )
    (net (code "76") (name "Net-(R198-Pad2)") (class "Default")
      (node (ref "R198") (pin "2") (pinfunction "2_2") (pintype "passive"))
      (node (ref "VT35") (pin "1") (pinfunction "1_1") (pintype "passive"))
    )
    (net (code "77") (name "unconnected-(DA56-NC-Pad3)") (class "Default")
      (node (ref "DA56") (pin "3") (pinfunction "NC_3") (pintype "passive+no_connect"))
    )
    (net (code "78") (name "unconnected-(DA57-NC-Pad3)") (class "Default")
      (node (ref "DA57") (pin "3") (pinfunction "NC_3") (pintype "passive+no_connect"))
    )
    (net (code "79") (name "unconnected-(DA58-NC-Pad3)") (class "Default")
      (node (ref "DA58") (pin "3") (pinfunction "NC_3") (pintype "passive+no_connect"))
    )
    (net (code "80") (name "unconnected-(DA62-NC-Pad3)") (class "Default")
      (node (ref "DA62") (pin "3") (pinfunction "NC_3") (pintype "passive+no_connect"))
    )
    (net (code "81") (name "unconnected-(DA63-NC-Pad3)") (class "Default")
      (node (ref "DA63") (pin "3") (pinfunction "NC_3") (pintype "passive+no_connect"))
    )
    (net (code "82") (name "unconnected-(DA64-NC-Pad3)") (class "Default")
      (node (ref "DA64") (pin "3") (pinfunction "NC_3") (pintype "passive+no_connect"))
    )
    (net (code "83") (name "unconnected-(DA68-NC-Pad3)") (class "Default")
      (node (ref "DA68") (pin "3") (pinfunction "NC_3") (pintype "passive+no_connect"))
    )
    (net (code "84") (name "unconnected-(DA69-NC-Pad3)") (class "Default")
      (node (ref "DA69") (pin "3") (pinfunction "NC_3") (pintype "passive+no_connect"))
    )
    (net (code "85") (name "unconnected-(DA70-NC-Pad3)") (class "Default")
      (node (ref "DA70") (pin "3") (pinfunction "NC_3") (pintype "passive+no_connect"))
    )
  )
)
